# NFC_Module.net
KiCad netlist of a schematic drawn in EasyEDA Pro
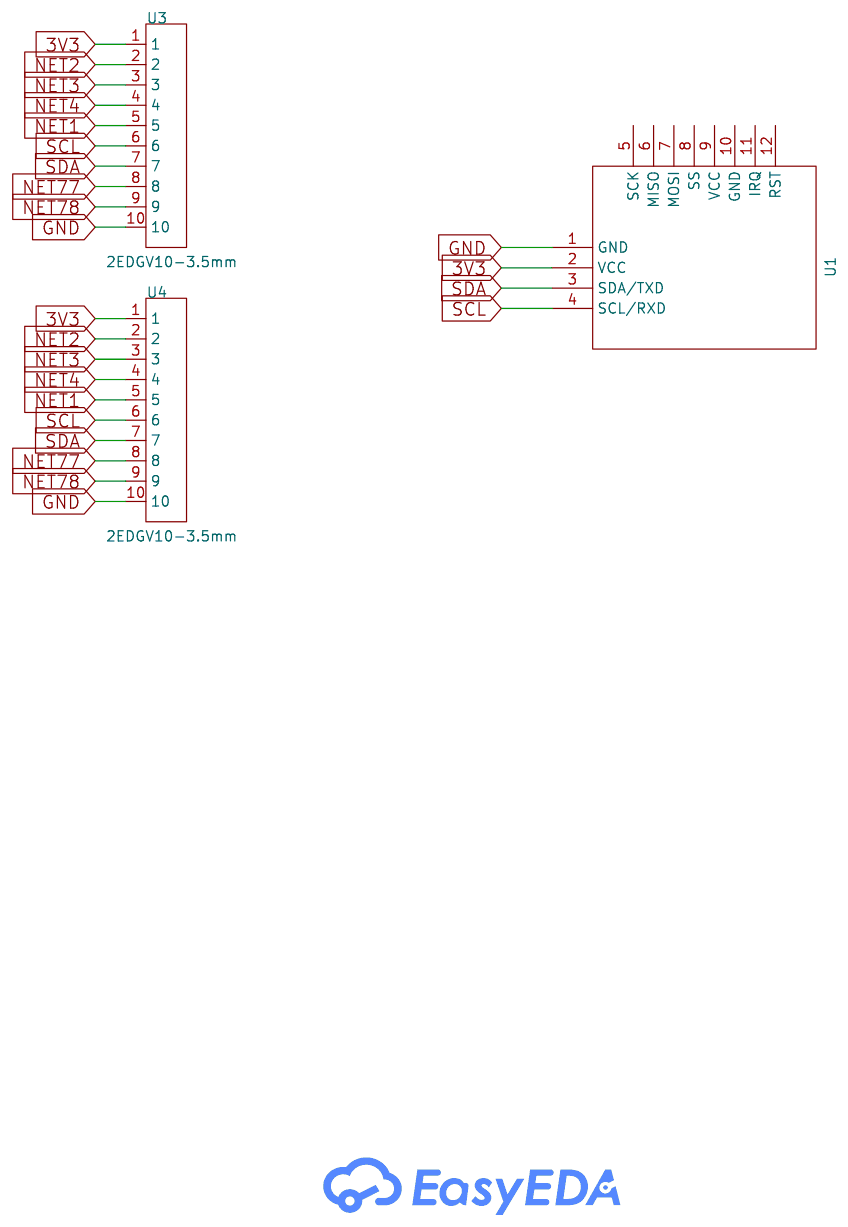
[diagram p0: schematic sheet]

(export (version "E")
  (design (tool "Eeschema 10.0.6"))
  (components
    (comp (ref "U1") (value "~") (footprint "easyedapro:PN532") (libsource (lib "easyedapro") (part "PN532")))
    (comp (ref "U3")
      (value "2EDGV10-3.5mm")
      (footprint "easyedapro:CONN-TH_10P-P3.50")
      (libsource (lib "easyedapro") (part "CONN-TH_10P-P3.50"))
    )
    (comp (ref "U4")
      (value "2EDGV10-3.5mm")
      (footprint "easyedapro:CONN-TH_10P-P3.50")
      (libsource (lib "easyedapro") (part "CONN-TH_10P-P3.50"))
    )
  )
  (nets
    (net (code "1") (name "3V3") (class "Default")
      (node (ref "U1") (pin "2") (pinfunction "VCC_2") (pintype "input"))
      (node (ref "U3") (pin "1") (pinfunction "1_1") (pintype "unspecified"))
      (node (ref "U4") (pin "1") (pinfunction "1_1") (pintype "unspecified"))
    )
    (net (code "2") (name "GND") (class "Default")
      (node (ref "U1") (pin "1") (pinfunction "GND_1") (pintype "input"))
      (node (ref "U3") (pin "10") (pinfunction "10_10") (pintype "unspecified"))
      (node (ref "U4") (pin "10") (pinfunction "10_10") (pintype "unspecified"))
    )
    (net (code "3") (name "NET1") (class "Default")
      (node (ref "U3") (pin "5") (pinfunction "5_5") (pintype "unspecified"))
      (node (ref "U4") (pin "5") (pinfunction "5_5") (pintype "unspecified"))
    )
    (net (code "4") (name "NET2") (class "Default")
      (node (ref "U3") (pin "2") (pinfunction "2_2") (pintype "unspecified"))
      (node (ref "U4") (pin "2") (pinfunction "2_2") (pintype "unspecified"))
    )
    (net (code "5") (name "NET3") (class "Default")
      (node (ref "U3") (pin "3") (pinfunction "3_3") (pintype "unspecified"))
      (node (ref "U4") (pin "3") (pinfunction "3_3") (pintype "unspecified"))
    )
    (net (code "6") (name "NET4") (class "Default")
      (node (ref "U3") (pin "4") (pinfunction "4_4") (pintype "unspecified"))
      (node (ref "U4") (pin "4") (pinfunction "4_4") (pintype "unspecified"))
    )
    (net (code "7") (name "NET77") (class "Default")
      (node (ref "U3") (pin "8") (pinfunction "8_8") (pintype "unspecified"))
      (node (ref "U4") (pin "8") (pinfunction "8_8") (pintype "unspecified"))
    )
    (net (code "8") (name "NET78") (class "Default")
      (node (ref "U3") (pin "9") (pinfunction "9_9") (pintype "unspecified"))
      (node (ref "U4") (pin "9") (pinfunction "9_9") (pintype "unspecified"))
    )
    (net (code "9") (name "SCL") (class "Default")
      (node (ref "U1") (pin "4") (pinfunction "SCL/RXD_4") (pintype "input"))
      (node (ref "U3") (pin "6") (pinfunction "6_6") (pintype "unspecified"))
      (node (ref "U4") (pin "6") (pinfunction "6_6") (pintype "unspecified"))
    )
    (net (code "10") (name "SDA") (class "Default")
      (node (ref "U1") (pin "3") (pinfunction "SDA/TXD_3") (pintype "input"))
      (node (ref "U3") (pin "7") (pinfunction "7_7") (pintype "unspecified"))
      (node (ref "U4") (pin "7") (pinfunction "7_7") (pintype "unspecified"))
    )
    (net (code "11") (name "unconnected-(U1-GND-Pad10)") (class "Default")
      (node (ref "U1") (pin "10") (pinfunction "GND_10") (pintype "input"))
    )
    (net (code "12") (name "unconnected-(U1-IRQ-Pad11)") (class "Default")
      (node (ref "U1") (pin "11") (pinfunction "IRQ_11") (pintype "input"))
    )
    (net (code "13") (name "unconnected-(U1-MISO-Pad6)") (class "Default")
      (node (ref "U1") (pin "6") (pinfunction "MISO_6") (pintype "input"))
    )
    (net (code "14") (name "unconnected-(U1-MOSI-Pad7)") (class "Default")
      (node (ref "U1") (pin "7") (pinfunction "MOSI_7") (pintype "input"))
    )
    (net (code "15") (name "unconnected-(U1-RST-Pad12)") (class "Default")
      (node (ref "U1") (pin "12") (pinfunction "RST_12") (pintype "input"))
    )
    (net (code "16") (name "unconnected-(U1-SCK-Pad5)") (class "Default")
      (node (ref "U1") (pin "5") (pinfunction "SCK_5") (pintype "input"))
    )
    (net (code "17") (name "unconnected-(U1-SS-Pad8)") (class "Default")
      (node (ref "U1") (pin "8") (pinfunction "SS_8") (pintype "input"))
    )
    (net (code "18") (name "unconnected-(U1-VCC-Pad9)") (class "Default")
      (node (ref "U1") (pin "9") (pinfunction "VCC_9") (pintype "input"))
    )
  )
)
